# EnsembleSeven.net
KiCad netlist of a schematic drawn in EAGLE
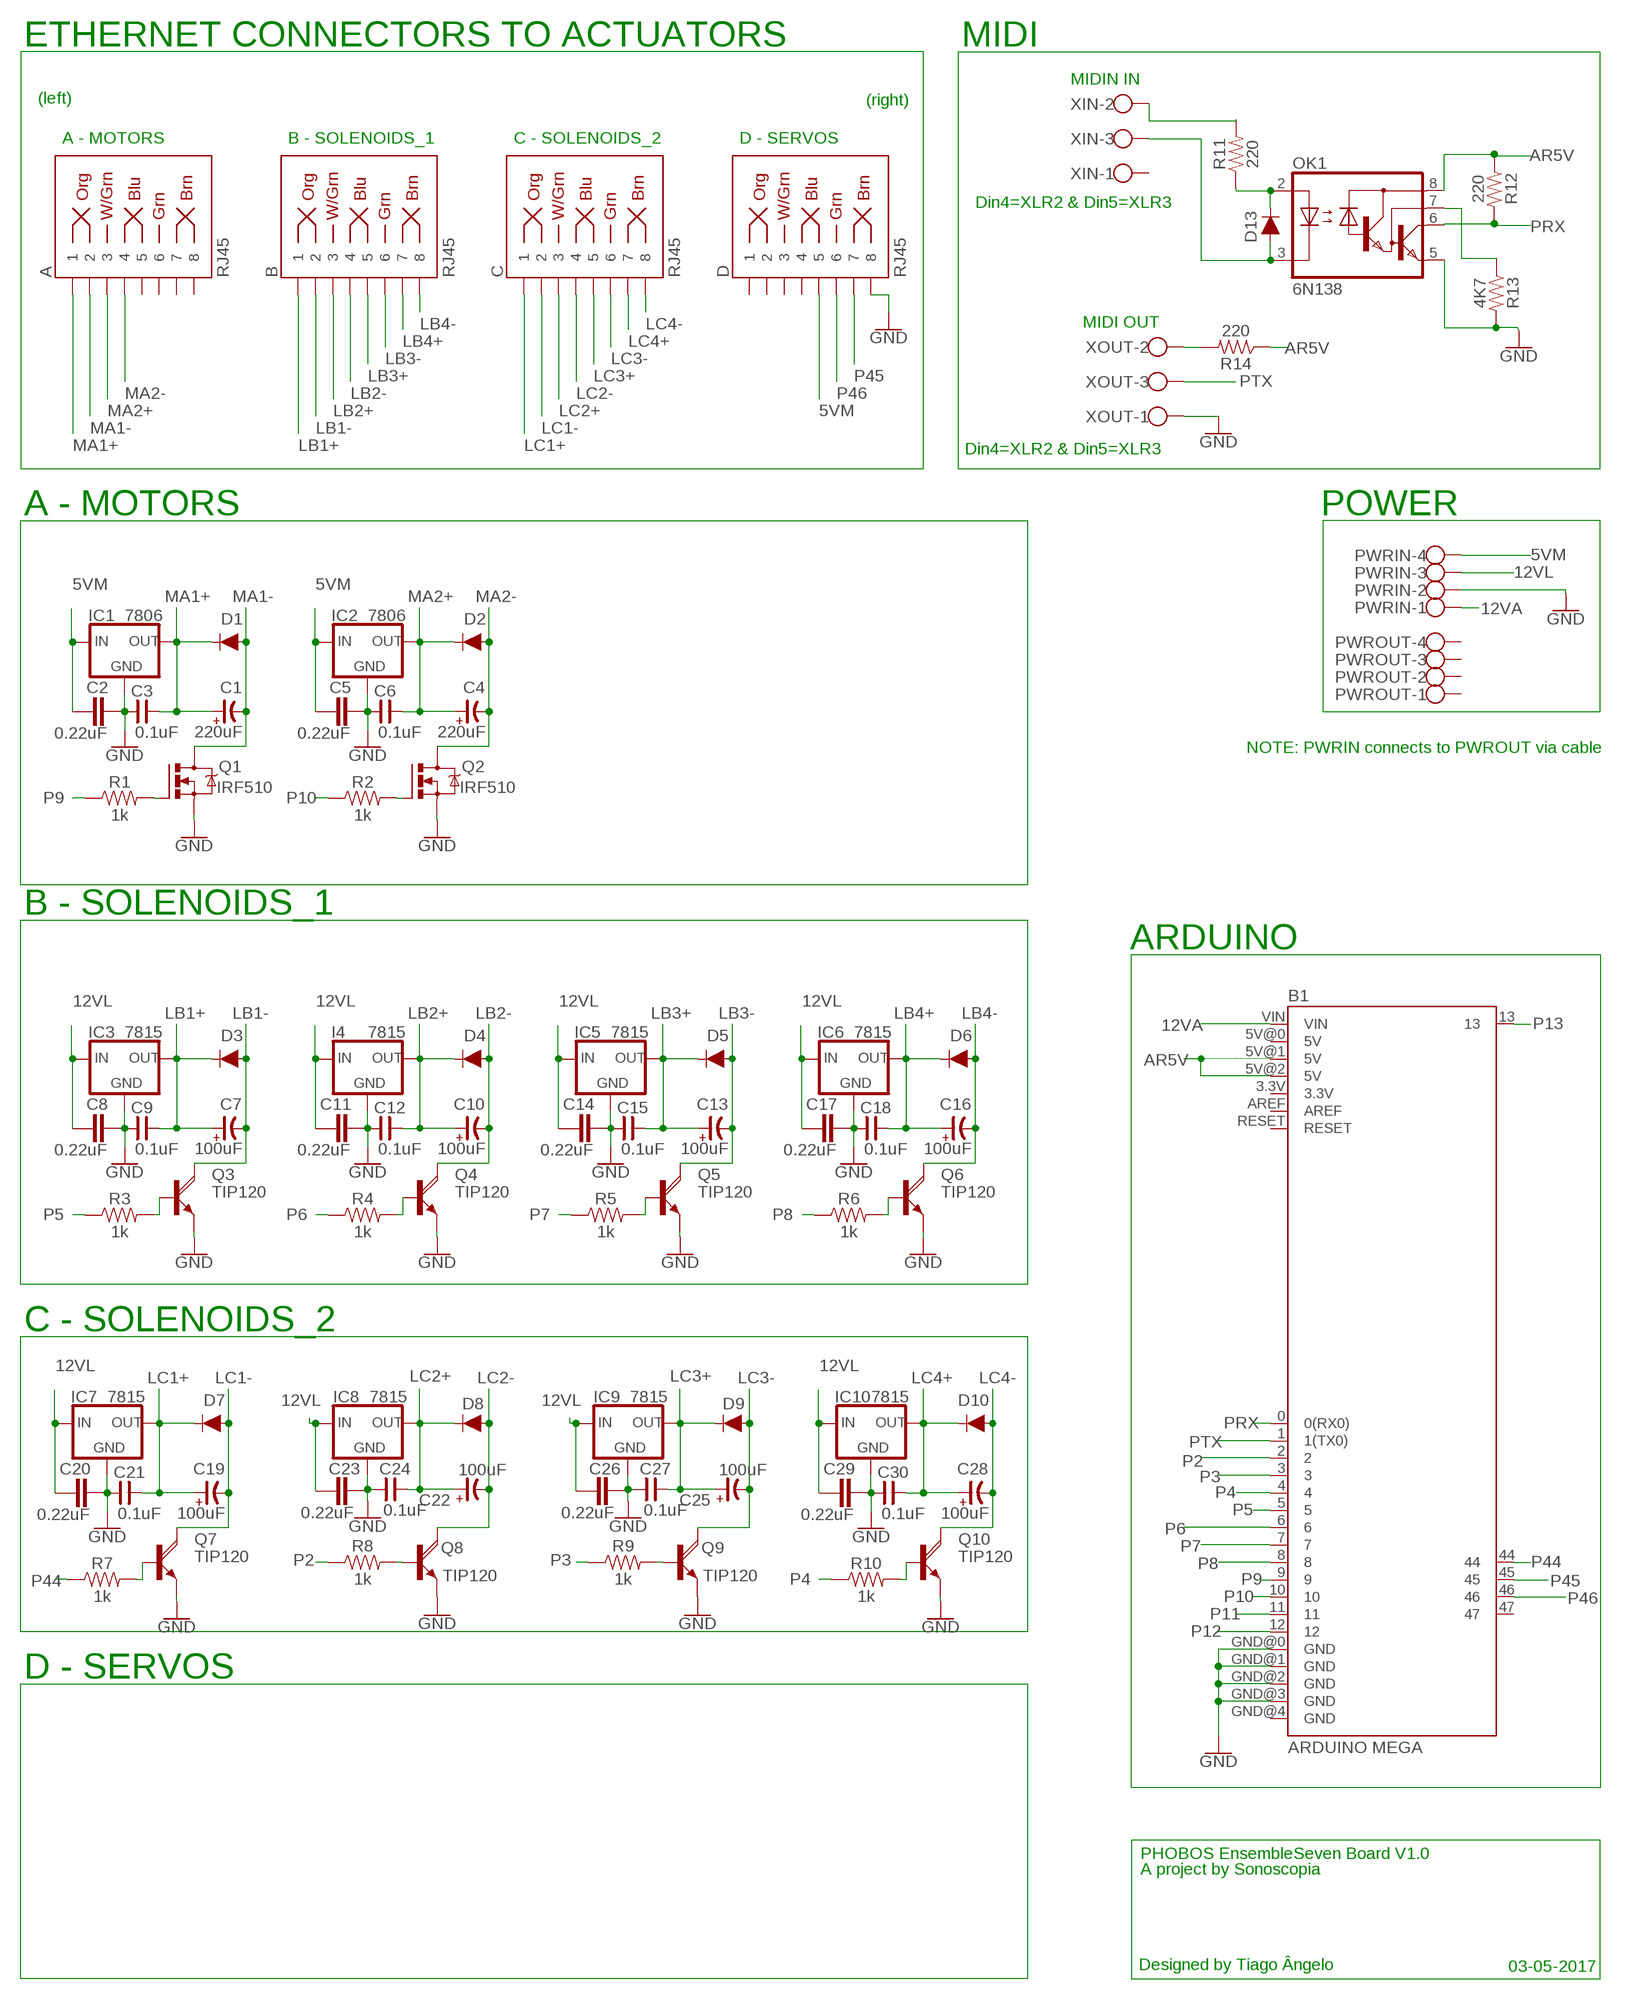
[diagram p0: schematic, sheet 1]

(export (version "E")
  (design (tool "Eeschema 10.0.6"))
  (components
    (comp (ref "A")
      (value "RJ45")
      (footprint "eagle-import:RJ45-8")
      (libsource (lib "eagle-import") (part "RJ45-8"))
    )
    (comp (ref "B")
      (value "RJ45")
      (footprint "eagle-import:RJ45-8")
      (libsource (lib "eagle-import") (part "RJ45-8"))
    )
    (comp (ref "B1")
      (value "ARDUINO MEGA")
      (footprint "eagle-import:ARDUINO_MEGA")
      (libsource (lib "eagle-import") (part "ARDUINO_MEGA_R3FULL"))
    )
    (comp (ref "C")
      (value "RJ45")
      (footprint "eagle-import:RJ45-8")
      (libsource (lib "eagle-import") (part "RJ45-8"))
    )
    (comp (ref "C1")
      (value "220uF")
      (footprint "eagle-import:E-035X080")
      (libsource (lib "eagle-import") (part "CP-E-035X080"))
    )
    (comp (ref "C2")
      (value "0.22uF")
      (footprint "eagle-import:C5B3")
      (libsource (lib "eagle-import") (part "C5/3"))
    )
    (comp (ref "C3")
      (value "0.1uF")
      (footprint "eagle-import:C025-050X025")
      (libsource (lib "eagle-import") (part "CNP-C025-050X025"))
    )
    (comp (ref "C4")
      (value "220uF")
      (footprint "eagle-import:E-035X080")
      (libsource (lib "eagle-import") (part "CP-E-035X080"))
    )
    (comp (ref "C5")
      (value "0.22uF")
      (footprint "eagle-import:C5B3")
      (libsource (lib "eagle-import") (part "C5/3"))
    )
    (comp (ref "C6")
      (value "0.1uF")
      (footprint "eagle-import:C025-050X025")
      (libsource (lib "eagle-import") (part "CNP-C025-050X025"))
    )
    (comp (ref "C7")
      (value "100uF")
      (footprint "eagle-import:CAP-MASTER_E-020X050")
      (libsource (lib "eagle-import") (part "CAP-MASTER_CP-E-020X050"))
    )
    (comp (ref "C8")
      (value "0.22uF")
      (footprint "eagle-import:C5B3")
      (libsource (lib "eagle-import") (part "C5/3"))
    )
    (comp (ref "C9")
      (value "0.1uF")
      (footprint "eagle-import:C025-050X025")
      (libsource (lib "eagle-import") (part "CNP-C025-050X025"))
    )
    (comp (ref "C10")
      (value "100uF")
      (footprint "eagle-import:CAP-MASTER_E-020X050")
      (libsource (lib "eagle-import") (part "CAP-MASTER_CP-E-020X050"))
    )
    (comp (ref "C11")
      (value "0.22uF")
      (footprint "eagle-import:C5B3")
      (libsource (lib "eagle-import") (part "C5/3"))
    )
    (comp (ref "C12")
      (value "0.1uF")
      (footprint "eagle-import:C025-050X025")
      (libsource (lib "eagle-import") (part "CNP-C025-050X025"))
    )
    (comp (ref "C13")
      (value "100uF")
      (footprint "eagle-import:CAP-MASTER_E-020X050")
      (libsource (lib "eagle-import") (part "CAP-MASTER_CP-E-020X050"))
    )
    (comp (ref "C14")
      (value "0.22uF")
      (footprint "eagle-import:C5B3")
      (libsource (lib "eagle-import") (part "C5/3"))
    )
    (comp (ref "C15")
      (value "0.1uF")
      (footprint "eagle-import:C025-050X025")
      (libsource (lib "eagle-import") (part "CNP-C025-050X025"))
    )
    (comp (ref "C16")
      (value "100uF")
      (footprint "eagle-import:CAP-MASTER_E-020X050")
      (libsource (lib "eagle-import") (part "CAP-MASTER_CP-E-020X050"))
    )
    (comp (ref "C17")
      (value "0.22uF")
      (footprint "eagle-import:C5B3")
      (libsource (lib "eagle-import") (part "C5/3"))
    )
    (comp (ref "C18")
      (value "0.1uF")
      (footprint "eagle-import:C025-050X025")
      (libsource (lib "eagle-import") (part "CNP-C025-050X025"))
    )
    (comp (ref "C19")
      (value "100uF")
      (footprint "eagle-import:CAP-MASTER_E-020X050")
      (libsource (lib "eagle-import") (part "CAP-MASTER_CP-E-020X050"))
    )
    (comp (ref "C20")
      (value "0.22uF")
      (footprint "eagle-import:C5B3")
      (libsource (lib "eagle-import") (part "C5/3"))
    )
    (comp (ref "C21")
      (value "0.1uF")
      (footprint "eagle-import:C025-050X025")
      (libsource (lib "eagle-import") (part "CNP-C025-050X025"))
    )
    (comp (ref "C22")
      (value "100uF")
      (footprint "eagle-import:E-020X050")
      (libsource (lib "eagle-import") (part "CP-E-020X050"))
    )
    (comp (ref "C23")
      (value "0.22uF")
      (footprint "eagle-import:C5B3")
      (libsource (lib "eagle-import") (part "C5/3"))
    )
    (comp (ref "C24")
      (value "0.1uF")
      (footprint "eagle-import:C025-050X025")
      (libsource (lib "eagle-import") (part "CNP-C025-050X025"))
    )
    (comp (ref "C25")
      (value "100uF")
      (footprint "eagle-import:E-020X050")
      (libsource (lib "eagle-import") (part "CP-E-020X050"))
    )
    (comp (ref "C26")
      (value "0.22uF")
      (footprint "eagle-import:C5B3")
      (libsource (lib "eagle-import") (part "C5/3"))
    )
    (comp (ref "C27")
      (value "0.1uF")
      (footprint "eagle-import:C025-050X025")
      (libsource (lib "eagle-import") (part "CNP-C025-050X025"))
    )
    (comp (ref "C28")
      (value "100uF")
      (footprint "eagle-import:CAP-MASTER_E-020X050")
      (libsource (lib "eagle-import") (part "CAP-MASTER_CP-E-020X050"))
    )
    (comp (ref "C29")
      (value "0.22uF")
      (footprint "eagle-import:C5B3")
      (libsource (lib "eagle-import") (part "C5/3"))
    )
    (comp (ref "C30")
      (value "0.1uF")
      (footprint "eagle-import:C025-050X025")
      (libsource (lib "eagle-import") (part "CNP-C025-050X025"))
    )
    (comp (ref "D")
      (value "RJ45")
      (footprint "eagle-import:RJ45-8")
      (libsource (lib "eagle-import") (part "RJ45-8"))
    )
    (comp (ref "D1")
      (value "1A/50V/1.1V")
      (footprint "eagle-import:DIODE-1N4001-KIT")
      (libsource (lib "eagle-import") (part "DIODE-KIT2"))
    )
    (comp (ref "D2")
      (value "1A/50V/1.1V")
      (footprint "eagle-import:DIODE-1N4001-KIT")
      (libsource (lib "eagle-import") (part "DIODE-KIT2"))
    )
    (comp (ref "D3")
      (value "1A/50V/1.1V")
      (footprint "eagle-import:DIODE-1N4001-KIT")
      (libsource (lib "eagle-import") (part "DIODE-KIT2"))
    )
    (comp (ref "D4")
      (value "1A/50V/1.1V")
      (footprint "eagle-import:DIODE-1N4001-KIT")
      (libsource (lib "eagle-import") (part "DIODE-KIT2"))
    )
    (comp (ref "D5")
      (value "1A/50V/1.1V")
      (footprint "eagle-import:DIODE-1N4001-KIT")
      (libsource (lib "eagle-import") (part "DIODE-KIT2"))
    )
    (comp (ref "D6")
      (value "1A/50V/1.1V")
      (footprint "eagle-import:DIODE-1N4001-KIT")
      (libsource (lib "eagle-import") (part "DIODE-KIT2"))
    )
    (comp (ref "D7")
      (value "1A/50V/1.1V")
      (footprint "eagle-import:DIODE-1N4001-KIT")
      (libsource (lib "eagle-import") (part "DIODE-KIT2"))
    )
    (comp (ref "D8")
      (value "1A/50V/1.1V")
      (footprint "eagle-import:DIODE-1N4001-KIT")
      (libsource (lib "eagle-import") (part "DIODE-KIT2"))
    )
    (comp (ref "D9")
      (value "1A/50V/1.1V")
      (footprint "eagle-import:DIODE-1N4001-KIT")
      (libsource (lib "eagle-import") (part "DIODE-KIT2"))
    )
    (comp (ref "D10")
      (value "1A/50V/1.1V")
      (footprint "eagle-import:DIODE-1N4001-KIT")
      (libsource (lib "eagle-import") (part "DIODE-KIT2"))
    )
    (comp (ref "D13")
      (value "200mA/100V/1V")
      (footprint "eagle-import:DIODE-1N4148")
      (libsource (lib "eagle-import") (part "DIODE-1N4148"))
    )
    (comp (ref "I4")
      (value "7815")
      (footprint "eagle-import:78XXS")
      (libsource (lib "eagle-import") (part "78XXS"))
    )
    (comp (ref "IC1")
      (value "7806")
      (footprint "eagle-import:78XXS")
      (libsource (lib "eagle-import") (part "78XXS"))
    )
    (comp (ref "IC2")
      (value "7806")
      (footprint "eagle-import:78XXS")
      (libsource (lib "eagle-import") (part "78XXS"))
    )
    (comp (ref "IC3")
      (value "7815")
      (footprint "eagle-import:78XXS")
      (libsource (lib "eagle-import") (part "78XXS"))
    )
    (comp (ref "IC5")
      (value "7815")
      (footprint "eagle-import:78XXS")
      (libsource (lib "eagle-import") (part "78XXS"))
    )
    (comp (ref "IC6")
      (value "7815")
      (footprint "eagle-import:78XXS")
      (libsource (lib "eagle-import") (part "78XXS"))
    )
    (comp (ref "IC7")
      (value "7815")
      (footprint "eagle-import:78XXS")
      (libsource (lib "eagle-import") (part "78XXS"))
    )
    (comp (ref "IC8")
      (value "7815")
      (footprint "eagle-import:78XXS")
      (libsource (lib "eagle-import") (part "78XXS"))
    )
    (comp (ref "IC9")
      (value "7815")
      (footprint "eagle-import:78XXS")
      (libsource (lib "eagle-import") (part "78XXS"))
    )
    (comp (ref "IC10")
      (value "7815")
      (footprint "eagle-import:78XXS")
      (libsource (lib "eagle-import") (part "78XXS"))
    )
    (comp (ref "OK1")
      (value "6N138")
      (footprint "eagle-import:DIL08")
      (fields (field (name "MF") "VISHAY/TELEFUNKEN"))
      (libsource (lib "eagle-import") (part "6N138"))
    )
    (comp (ref "PWRIN")
      (value "W237-4")
      (footprint "eagle-import:W237-4")
      (libsource (lib "eagle-import") (part "W237-4"))
    )
    (comp (ref "PWROUT")
      (value "W237-4")
      (footprint "eagle-import:W237-4")
      (libsource (lib "eagle-import") (part "W237-4"))
    )
    (comp (ref "Q1")
      (value "IRF510")
      (footprint "eagle-import:TO220BV")
      (libsource (lib "eagle-import") (part "IRF520"))
    )
    (comp (ref "Q2")
      (value "IRF510")
      (footprint "eagle-import:TO220BV")
      (libsource (lib "eagle-import") (part "IRF520"))
    )
    (comp (ref "Q3")
      (value "TIP120")
      (footprint "eagle-import:ROCKETFARM_TO220AV")
      (libsource (lib "eagle-import") (part "ROCKETFARM_TIP120V"))
    )
    (comp (ref "Q4")
      (value "TIP120")
      (footprint "eagle-import:ROCKETFARM_TO220AV")
      (libsource (lib "eagle-import") (part "ROCKETFARM_TIP120V"))
    )
    (comp (ref "Q5")
      (value "TIP120")
      (footprint "eagle-import:ROCKETFARM_TO220AV")
      (libsource (lib "eagle-import") (part "ROCKETFARM_TIP120V"))
    )
    (comp (ref "Q6")
      (value "TIP120")
      (footprint "eagle-import:ROCKETFARM_TO220AV")
      (libsource (lib "eagle-import") (part "ROCKETFARM_TIP120V"))
    )
    (comp (ref "Q7")
      (value "TIP120")
      (footprint "eagle-import:ROCKETFARM_TO220AV")
      (libsource (lib "eagle-import") (part "ROCKETFARM_TIP120V"))
    )
    (comp (ref "Q8")
      (value "TIP120")
      (footprint "eagle-import:TO220AV")
      (libsource (lib "eagle-import") (part "TIP120V"))
    )
    (comp (ref "Q9")
      (value "TIP120")
      (footprint "eagle-import:TO220AV")
      (libsource (lib "eagle-import") (part "TIP120V"))
    )
    (comp (ref "Q10")
      (value "TIP120")
      (footprint "eagle-import:ROCKETFARM_TO220AV")
      (libsource (lib "eagle-import") (part "ROCKETFARM_TIP120V"))
    )
    (comp (ref "R1")
      (value "1k")
      (footprint "eagle-import:AXIAL-0.1")
      (libsource (lib "eagle-import") (part "1KOHM-VERT-1/4W-1%"))
    )
    (comp (ref "R2")
      (value "1k")
      (footprint "eagle-import:AXIAL-0.1")
      (libsource (lib "eagle-import") (part "1KOHM-VERT-1/4W-1%"))
    )
    (comp (ref "R3")
      (value "1k")
      (footprint "eagle-import:AXIAL-0.1")
      (libsource (lib "eagle-import") (part "1KOHM-VERT-1/4W-1%"))
    )
    (comp (ref "R4")
      (value "1k")
      (footprint "eagle-import:AXIAL-0.1")
      (libsource (lib "eagle-import") (part "1KOHM-VERT-1/4W-1%"))
    )
    (comp (ref "R5")
      (value "1k")
      (footprint "eagle-import:AXIAL-0.1")
      (libsource (lib "eagle-import") (part "1KOHM-VERT-1/4W-1%"))
    )
    (comp (ref "R6")
      (value "1k")
      (footprint "eagle-import:AXIAL-0.1")
      (libsource (lib "eagle-import") (part "1KOHM-VERT-1/4W-1%"))
    )
    (comp (ref "R7")
      (value "1k")
      (footprint "eagle-import:AXIAL-0.1")
      (libsource (lib "eagle-import") (part "1KOHM-VERT-1/4W-1%"))
    )
    (comp (ref "R8")
      (value "1k")
      (footprint "eagle-import:AXIAL-0.1")
      (libsource (lib "eagle-import") (part "1KOHM-VERT-1/4W-1%"))
    )
    (comp (ref "R9")
      (value "1k")
      (footprint "eagle-import:AXIAL-0.1")
      (libsource (lib "eagle-import") (part "1KOHM-VERT-1/4W-1%"))
    )
    (comp (ref "R10")
      (value "1k")
      (footprint "eagle-import:AXIAL-0.1")
      (libsource (lib "eagle-import") (part "1KOHM-VERT-1/4W-1%"))
    )
    (comp (ref "R11")
      (value "220")
      (footprint "eagle-import:AXIAL-0.3")
      (libsource (lib "eagle-import") (part "1KOHM-HORIZ-1/4W-5%"))
    )
    (comp (ref "R12")
      (value "220")
      (footprint "eagle-import:AXIAL-0.3")
      (libsource (lib "eagle-import") (part "1KOHM-HORIZ-1/4W-5%"))
    )
    (comp (ref "R13")
      (value "4K7")
      (footprint "eagle-import:AXIAL-0.3")
      (libsource (lib "eagle-import") (part "1KOHM-HORIZ-1/4W-5%"))
    )
    (comp (ref "R14")
      (value "220")
      (footprint "eagle-import:AXIAL-0.3")
      (libsource (lib "eagle-import") (part "1KOHM-HORIZ-1/4W-5%"))
    )
    (comp (ref "XIN")
      (value "W237-103")
      (footprint "eagle-import:W237-103")
      (fields (field (name "MPN") "237-103"))
      (libsource (lib "eagle-import") (part "W237-103"))
    )
    (comp (ref "XOUT")
      (value "W237-103")
      (footprint "eagle-import:W237-103")
      (fields (field (name "MPN") "237-103"))
      (libsource (lib "eagle-import") (part "W237-103"))
    )
  )
  (nets
    (net (code "1") (name "/5VM") (class "Default")
      (node (ref "C2") (pin "1") (pinfunction "1_1") (pintype "passive"))
      (node (ref "C5") (pin "1") (pinfunction "1_1") (pintype "passive"))
      (node (ref "D") (pin "5") (pinfunction "5_5") (pintype "bidirectional"))
      (node (ref "IC1") (pin "IN") (pinfunction "IN_IN") (pintype "input"))
      (node (ref "IC2") (pin "IN") (pinfunction "IN_IN") (pintype "input"))
      (node (ref "PWRIN") (pin "4") (pinfunction "KL_4") (pintype "passive"))
    )
    (net (code "2") (name "/12VA") (class "Default")
      (node (ref "B1") (pin "VIN") (pinfunction "VIN_VIN") (pintype "bidirectional"))
      (node (ref "PWRIN") (pin "1") (pinfunction "KL_1") (pintype "passive"))
    )
    (net (code "3") (name "/12VL") (class "Default")
      (node (ref "C11") (pin "1") (pinfunction "1_1") (pintype "passive"))
      (node (ref "C14") (pin "1") (pinfunction "1_1") (pintype "passive"))
      (node (ref "C17") (pin "1") (pinfunction "1_1") (pintype "passive"))
      (node (ref "C20") (pin "1") (pinfunction "1_1") (pintype "passive"))
      (node (ref "C23") (pin "1") (pinfunction "1_1") (pintype "passive"))
      (node (ref "C26") (pin "1") (pinfunction "1_1") (pintype "passive"))
      (node (ref "C29") (pin "1") (pinfunction "1_1") (pintype "passive"))
      (node (ref "C8") (pin "1") (pinfunction "1_1") (pintype "passive"))
      (node (ref "I4") (pin "IN") (pinfunction "IN_IN") (pintype "input"))
      (node (ref "IC10") (pin "IN") (pinfunction "IN_IN") (pintype "input"))
      (node (ref "IC3") (pin "IN") (pinfunction "IN_IN") (pintype "input"))
      (node (ref "IC5") (pin "IN") (pinfunction "IN_IN") (pintype "input"))
      (node (ref "IC6") (pin "IN") (pinfunction "IN_IN") (pintype "input"))
      (node (ref "IC7") (pin "IN") (pinfunction "IN_IN") (pintype "input"))
      (node (ref "IC8") (pin "IN") (pinfunction "IN_IN") (pintype "input"))
      (node (ref "IC9") (pin "IN") (pinfunction "IN_IN") (pintype "input"))
      (node (ref "PWRIN") (pin "3") (pinfunction "KL_3") (pintype "passive"))
    )
    (net (code "4") (name "/AR5V") (class "Default")
      (node (ref "B1") (pin "5V@1") (pinfunction "5V_5V@1") (pintype "bidirectional"))
      (node (ref "B1") (pin "5V@2") (pinfunction "5V_5V@2") (pintype "bidirectional"))
      (node (ref "OK1") (pin "8") (pinfunction "VCC_8") (pintype "passive"))
      (node (ref "R12") (pin "P$1") (pinfunction "1_P$1") (pintype "passive"))
      (node (ref "R14") (pin "P$1") (pinfunction "1_P$1") (pintype "passive"))
    )
    (net (code "5") (name "/LB1+") (class "Default")
      (node (ref "B") (pin "1") (pinfunction "1_1") (pintype "bidirectional"))
      (node (ref "C7") (pin "+") (pinfunction "+_+") (pintype "passive"))
      (node (ref "C9") (pin "2") (pinfunction "2_2") (pintype "passive"))
      (node (ref "D3") (pin "C") (pinfunction "C_C") (pintype "passive"))
      (node (ref "IC3") (pin "OUT") (pinfunction "OUT_OUT") (pintype "passive"))
    )
    (net (code "6") (name "/LB1-") (class "Default")
      (node (ref "B") (pin "2") (pinfunction "2_2") (pintype "bidirectional"))
      (node (ref "C7") (pin "-") (pinfunction "-_-") (pintype "passive"))
      (node (ref "D3") (pin "A") (pinfunction "A_A") (pintype "passive"))
      (node (ref "Q3") (pin "C") (pinfunction "C_C") (pintype "passive"))
    )
    (net (code "7") (name "/LB2+") (class "Default")
      (node (ref "B") (pin "3") (pinfunction "3_3") (pintype "bidirectional"))
      (node (ref "C10") (pin "+") (pinfunction "+_+") (pintype "passive"))
      (node (ref "C12") (pin "2") (pinfunction "2_2") (pintype "passive"))
      (node (ref "D4") (pin "C") (pinfunction "C_C") (pintype "passive"))
      (node (ref "I4") (pin "OUT") (pinfunction "OUT_OUT") (pintype "passive"))
    )
    (net (code "8") (name "/LB2-") (class "Default")
      (node (ref "B") (pin "4") (pinfunction "4_4") (pintype "bidirectional"))
      (node (ref "C10") (pin "-") (pinfunction "-_-") (pintype "passive"))
      (node (ref "D4") (pin "A") (pinfunction "A_A") (pintype "passive"))
      (node (ref "Q4") (pin "C") (pinfunction "C_C") (pintype "passive"))
    )
    (net (code "9") (name "/LB3+") (class "Default")
      (node (ref "B") (pin "5") (pinfunction "5_5") (pintype "bidirectional"))
      (node (ref "C13") (pin "+") (pinfunction "+_+") (pintype "passive"))
      (node (ref "C15") (pin "2") (pinfunction "2_2") (pintype "passive"))
      (node (ref "D5") (pin "C") (pinfunction "C_C") (pintype "passive"))
      (node (ref "IC5") (pin "OUT") (pinfunction "OUT_OUT") (pintype "passive"))
    )
    (net (code "10") (name "/LB3-") (class "Default")
      (node (ref "B") (pin "6") (pinfunction "6_6") (pintype "bidirectional"))
      (node (ref "C13") (pin "-") (pinfunction "-_-") (pintype "passive"))
      (node (ref "D5") (pin "A") (pinfunction "A_A") (pintype "passive"))
      (node (ref "Q5") (pin "C") (pinfunction "C_C") (pintype "passive"))
    )
    (net (code "11") (name "/LB4+") (class "Default")
      (node (ref "B") (pin "7") (pinfunction "7_7") (pintype "bidirectional"))
      (node (ref "C16") (pin "+") (pinfunction "+_+") (pintype "passive"))
      (node (ref "C18") (pin "2") (pinfunction "2_2") (pintype "passive"))
      (node (ref "D6") (pin "C") (pinfunction "C_C") (pintype "passive"))
      (node (ref "IC6") (pin "OUT") (pinfunction "OUT_OUT") (pintype "passive"))
    )
    (net (code "12") (name "/LB4-") (class "Default")
      (node (ref "B") (pin "8") (pinfunction "8_8") (pintype "bidirectional"))
      (node (ref "C16") (pin "-") (pinfunction "-_-") (pintype "passive"))
      (node (ref "D6") (pin "A") (pinfunction "A_A") (pintype "passive"))
      (node (ref "Q6") (pin "C") (pinfunction "C_C") (pintype "passive"))
    )
    (net (code "13") (name "/LC1+") (class "Default")
      (node (ref "C") (pin "1") (pinfunction "1_1") (pintype "bidirectional"))
      (node (ref "C19") (pin "+") (pinfunction "+_+") (pintype "passive"))
      (node (ref "C21") (pin "2") (pinfunction "2_2") (pintype "passive"))
      (node (ref "D7") (pin "C") (pinfunction "C_C") (pintype "passive"))
      (node (ref "IC7") (pin "OUT") (pinfunction "OUT_OUT") (pintype "passive"))
    )
    (net (code "14") (name "/LC1-") (class "Default")
      (node (ref "C") (pin "2") (pinfunction "2_2") (pintype "bidirectional"))
      (node (ref "C19") (pin "-") (pinfunction "-_-") (pintype "passive"))
      (node (ref "D7") (pin "A") (pinfunction "A_A") (pintype "passive"))
      (node (ref "Q7") (pin "C") (pinfunction "C_C") (pintype "passive"))
    )
    (net (code "15") (name "/LC2+") (class "Default")
      (node (ref "C") (pin "3") (pinfunction "3_3") (pintype "bidirectional"))
      (node (ref "C22") (pin "+") (pinfunction "+_+") (pintype "passive"))
      (node (ref "C24") (pin "2") (pinfunction "2_2") (pintype "passive"))
      (node (ref "D8") (pin "C") (pinfunction "C_C") (pintype "passive"))
      (node (ref "IC8") (pin "OUT") (pinfunction "OUT_OUT") (pintype "passive"))
    )
    (net (code "16") (name "/LC2-") (class "Default")
      (node (ref "C") (pin "4") (pinfunction "4_4") (pintype "bidirectional"))
      (node (ref "C22") (pin "-") (pinfunction "-_-") (pintype "passive"))
      (node (ref "D8") (pin "A") (pinfunction "A_A") (pintype "passive"))
      (node (ref "Q8") (pin "C") (pinfunction "C_C") (pintype "passive"))
    )
    (net (code "17") (name "/LC3+") (class "Default")
      (node (ref "C") (pin "5") (pinfunction "5_5") (pintype "bidirectional"))
      (node (ref "C25") (pin "+") (pinfunction "+_+") (pintype "passive"))
      (node (ref "C27") (pin "2") (pinfunction "2_2") (pintype "passive"))
      (node (ref "D9") (pin "C") (pinfunction "C_C") (pintype "passive"))
      (node (ref "IC9") (pin "OUT") (pinfunction "OUT_OUT") (pintype "passive"))
    )
    (net (code "18") (name "/LC3-") (class "Default")
      (node (ref "C") (pin "6") (pinfunction "6_6") (pintype "bidirectional"))
      (node (ref "C25") (pin "-") (pinfunction "-_-") (pintype "passive"))
      (node (ref "D9") (pin "A") (pinfunction "A_A") (pintype "passive"))
      (node (ref "Q9") (pin "C") (pinfunction "C_C") (pintype "passive"))
    )
    (net (code "19") (name "/LC4+") (class "Default")
      (node (ref "C") (pin "7") (pinfunction "7_7") (pintype "bidirectional"))
      (node (ref "C28") (pin "+") (pinfunction "+_+") (pintype "passive"))
      (node (ref "C30") (pin "2") (pinfunction "2_2") (pintype "passive"))
      (node (ref "D10") (pin "C") (pinfunction "C_C") (pintype "passive"))
      (node (ref "IC10") (pin "OUT") (pinfunction "OUT_OUT") (pintype "passive"))
    )
    (net (code "20") (name "/LC4-") (class "Default")
      (node (ref "C") (pin "8") (pinfunction "8_8") (pintype "bidirectional"))
      (node (ref "C28") (pin "-") (pinfunction "-_-") (pintype "passive"))
      (node (ref "D10") (pin "A") (pinfunction "A_A") (pintype "passive"))
      (node (ref "Q10") (pin "C") (pinfunction "C_C") (pintype "passive"))
    )
    (net (code "21") (name "/MA1+") (class "Default")
      (node (ref "A") (pin "1") (pinfunction "1_1") (pintype "bidirectional"))
      (node (ref "C1") (pin "+") (pinfunction "+_+") (pintype "passive"))
      (node (ref "C3") (pin "2") (pinfunction "2_2") (pintype "passive"))
      (node (ref "D1") (pin "C") (pinfunction "C_C") (pintype "passive"))
      (node (ref "IC1") (pin "OUT") (pinfunction "OUT_OUT") (pintype "passive"))
    )
    (net (code "22") (name "/MA1-") (class "Default")
      (node (ref "A") (pin "2") (pinfunction "2_2") (pintype "bidirectional"))
      (node (ref "C1") (pin "-") (pinfunction "-_-") (pintype "passive"))
      (node (ref "D1") (pin "A") (pinfunction "A_A") (pintype "passive"))
      (node (ref "Q1") (pin "D") (pinfunction "D_D") (pintype "passive"))
    )
    (net (code "23") (name "/MA2+") (class "Default")
      (node (ref "A") (pin "3") (pinfunction "3_3") (pintype "bidirectional"))
      (node (ref "C4") (pin "+") (pinfunction "+_+") (pintype "passive"))
      (node (ref "C6") (pin "2") (pinfunction "2_2") (pintype "passive"))
      (node (ref "D2") (pin "C") (pinfunction "C_C") (pintype "passive"))
      (node (ref "IC2") (pin "OUT") (pinfunction "OUT_OUT") (pintype "passive"))
    )
    (net (code "24") (name "/MA2-") (class "Default")
      (node (ref "A") (pin "4") (pinfunction "4_4") (pintype "bidirectional"))
      (node (ref "C4") (pin "-") (pinfunction "-_-") (pintype "passive"))
      (node (ref "D2") (pin "A") (pinfunction "A_A") (pintype "passive"))
      (node (ref "Q2") (pin "D") (pinfunction "D_D") (pintype "passive"))
    )
    (net (code "25") (name "/P2") (class "Default")
      (node (ref "B1") (pin "2") (pinfunction "2_2") (pintype "bidirectional"))
      (node (ref "R8") (pin "P$1") (pinfunction "1_P$1") (pintype "passive"))
    )
    (net (code "26") (name "/P3") (class "Default")
      (node (ref "B1") (pin "3") (pinfunction "3_3") (pintype "bidirectional"))
      (node (ref "R9") (pin "P$1") (pinfunction "1_P$1") (pintype "passive"))
    )
    (net (code "27") (name "/P4") (class "Default")
      (node (ref "B1") (pin "4") (pinfunction "4_4") (pintype "bidirectional"))
      (node (ref "R10") (pin "P$1") (pinfunction "1_P$1") (pintype "passive"))
    )
    (net (code "28") (name "/P5") (class "Default")
      (node (ref "B1") (pin "5") (pinfunction "5_5") (pintype "bidirectional"))
      (node (ref "R3") (pin "P$1") (pinfunction "1_P$1") (pintype "passive"))
    )
    (net (code "29") (name "/P6") (class "Default")
      (node (ref "B1") (pin "6") (pinfunction "6_6") (pintype "bidirectional"))
      (node (ref "R4") (pin "P$1") (pinfunction "1_P$1") (pintype "passive"))
    )
    (net (code "30") (name "/P7") (class "Default")
      (node (ref "B1") (pin "7") (pinfunction "7_7") (pintype "bidirectional"))
      (node (ref "R5") (pin "P$1") (pinfunction "1_P$1") (pintype "passive"))
    )
    (net (code "31") (name "/P8") (class "Default")
      (node (ref "B1") (pin "8") (pinfunction "8_8") (pintype "bidirectional"))
      (node (ref "R6") (pin "P$1") (pinfunction "1_P$1") (pintype "passive"))
    )
    (net (code "32") (name "/P9") (class "Default")
      (node (ref "B1") (pin "9") (pinfunction "9_9") (pintype "bidirectional"))
      (node (ref "R1") (pin "P$1") (pinfunction "1_P$1") (pintype "passive"))
    )
    (net (code "33") (name "/P10") (class "Default")
      (node (ref "B1") (pin "10") (pinfunction "10_10") (pintype "bidirectional"))
      (node (ref "R2") (pin "P$1") (pinfunction "1_P$1") (pintype "passive"))
    )
    (net (code "34") (name "/P11") (class "Default")
      (node (ref "B1") (pin "11") (pinfunction "11_11") (pintype "bidirectional"))
    )
    (net (code "35") (name "/P12") (class "Default")
      (node (ref "B1") (pin "12") (pinfunction "12_12") (pintype "bidirectional"))
    )
    (net (code "36") (name "/P13") (class "Default")
      (node (ref "B1") (pin "13") (pinfunction "13_13") (pintype "bidirectional"))
    )
    (net (code "37") (name "/P44") (class "Default")
      (node (ref "B1") (pin "44") (pinfunction "44_44") (pintype "bidirectional"))
      (node (ref "R7") (pin "P$1") (pinfunction "1_P$1") (pintype "passive"))
    )
    (net (code "38") (name "/P45") (class "Default")
      (node (ref "B1") (pin "45") (pinfunction "45_45") (pintype "bidirectional"))
      (node (ref "D") (pin "7") (pinfunction "7_7") (pintype "bidirectional"))
    )
    (net (code "39") (name "/P46") (class "Default")
      (node (ref "B1") (pin "46") (pinfunction "46_46") (pintype "bidirectional"))
      (node (ref "D") (pin "6") (pinfunction "6_6") (pintype "bidirectional"))
    )
    (net (code "40") (name "/PRX") (class "Default")
      (node (ref "B1") (pin "0") (pinfunction "0(RX0)_0") (pintype "bidirectional"))
      (node (ref "OK1") (pin "6") (pinfunction "VO_6") (pintype "passive"))
      (node (ref "R12") (pin "P$2") (pinfunction "2_P$2") (pintype "passive"))
    )
    (net (code "41") (name "/PTX") (class "Default")
      (node (ref "B1") (pin "1") (pinfunction "1(TX0)_1") (pintype "bidirectional"))
      (node (ref "XOUT") (pin "3") (pinfunction "KL_3") (pintype "passive"))
    )
    (net (code "42") (name "GND") (class "Default")
      (node (ref "B1") (pin "GND@0") (pinfunction "GND_GND@0") (pintype "bidirectional"))
      (node (ref "B1") (pin "GND@1") (pinfunction "GND_GND@1") (pintype "bidirectional"))
      (node (ref "B1") (pin "GND@2") (pinfunction "GND_GND@2") (pintype "bidirectional"))
      (node (ref "B1") (pin "GND@3") (pinfunction "GND_GND@3") (pintype "bidirectional"))
      (node (ref "C11") (pin "2") (pinfunction "2_2") (pintype "passive"))
      (node (ref "C12") (pin "1") (pinfunction "1_1") (pintype "passive"))
      (node (ref "C14") (pin "2") (pinfunction "2_2") (pintype "passive"))
      (node (ref "C15") (pin "1") (pinfunction "1_1") (pintype "passive"))
      (node (ref "C17") (pin "2") (pinfunction "2_2") (pintype "passive"))
      (node (ref "C18") (pin "1") (pinfunction "1_1") (pintype "passive"))
      (node (ref "C2") (pin "2") (pinfunction "2_2") (pintype "passive"))
      (node (ref "C20") (pin "2") (pinfunction "2_2") (pintype "passive"))
      (node (ref "C21") (pin "1") (pinfunction "1_1") (pintype "passive"))
      (node (ref "C23") (pin "2") (pinfunction "2_2") (pintype "passive"))
      (node (ref "C24") (pin "1") (pinfunction "1_1") (pintype "passive"))
      (node (ref "C26") (pin "2") (pinfunction "2_2") (pintype "passive"))
      (node (ref "C27") (pin "1") (pinfunction "1_1") (pintype "passive"))
      (node (ref "C29") (pin "2") (pinfunction "2_2") (pintype "passive"))
      (node (ref "C3") (pin "1") (pinfunction "1_1") (pintype "passive"))
      (node (ref "C30") (pin "1") (pinfunction "1_1") (pintype "passive"))
      (node (ref "C5") (pin "2") (pinfunction "2_2") (pintype "passive"))
      (node (ref "C6") (pin "1") (pinfunction "1_1") (pintype "passive"))
      (node (ref "C8") (pin "2") (pinfunction "2_2") (pintype "passive"))
      (node (ref "C9") (pin "1") (pinfunction "1_1") (pintype "passive"))
      (node (ref "D") (pin "8") (pinfunction "8_8") (pintype "bidirectional"))
      (node (ref "I4") (pin "GND") (pinfunction "GND_GND") (pintype "input"))
      (node (ref "IC1") (pin "GND") (pinfunction "GND_GND") (pintype "input"))
      (node (ref "IC10") (pin "GND") (pinfunction "GND_GND") (pintype "input"))
      (node (ref "IC2") (pin "GND") (pinfunction "GND_GND") (pintype "input"))
      (node (ref "IC3") (pin "GND") (pinfunction "GND_GND") (pintype "input"))
      (node (ref "IC5") (pin "GND") (pinfunction "GND_GND") (pintype "input"))
      (node (ref "IC6") (pin "GND") (pinfunction "GND_GND") (pintype "input"))
      (node (ref "IC7") (pin "GND") (pinfunction "GND_GND") (pintype "input"))
      (node (ref "IC8") (pin "GND") (pinfunction "GND_GND") (pintype "input"))
      (node (ref "IC9") (pin "GND") (pinfunction "GND_GND") (pintype "input"))
      (node (ref "OK1") (pin "5") (pinfunction "GND_5") (pintype "passive"))
      (node (ref "PWRIN") (pin "2") (pinfunction "KL_2") (pintype "passive"))
      (node (ref "Q1") (pin "S") (pinfunction "S_S") (pintype "passive"))
      (node (ref "Q10") (pin "E") (pinfunction "E_E") (pintype "passive"))
      (node (ref "Q2") (pin "S") (pinfunction "S_S") (pintype "passive"))
      (node (ref "Q3") (pin "E") (pinfunction "E_E") (pintype "passive"))
      (node (ref "Q4") (pin "E") (pinfunction "E_E") (pintype "passive"))
      (node (ref "Q5") (pin "E") (pinfunction "E_E") (pintype "passive"))
      (node (ref "Q6") (pin "E") (pinfunction "E_E") (pintype "passive"))
      (node (ref "Q7") (pin "E") (pinfunction "E_E") (pintype "passive"))
      (node (ref "Q8") (pin "E") (pinfunction "E_E") (pintype "passive"))
      (node (ref "Q9") (pin "E") (pinfunction "E_E") (pintype "passive"))
      (node (ref "R13") (pin "P$2") (pinfunction "2_P$2") (pintype "passive"))
      (node (ref "XOUT") (pin "1") (pinfunction "KL_1") (pintype "passive"))
    )
    (net (code "43") (name "Net-(OK1-A)") (class "Default")
      (node (ref "D13") (pin "C") (pinfunction "C_C") (pintype "passive"))
      (node (ref "OK1") (pin "2") (pinfunction "A_2") (pintype "passive"))
      (node (ref "R11") (pin "P$1") (pinfunction "1_P$1") (pintype "passive"))
    )
    (net (code "44") (name "Net-(OK1-C)") (class "Default")
      (node (ref "D13") (pin "A") (pinfunction "A_A") (pintype "passive"))
      (node (ref "OK1") (pin "3") (pinfunction "C_3") (pintype "passive"))
      (node (ref "XIN") (pin "3") (pinfunction "KL_3") (pintype "passive"))
    )
    (net (code "45") (name "Net-(OK1-VB)") (class "Default")
      (node (ref "OK1") (pin "7") (pinfunction "VB_7") (pintype "passive"))
      (node (ref "R13") (pin "P$1") (pinfunction "1_P$1") (pintype "passive"))
    )
    (net (code "46") (name "Net-(R1-2)") (class "Default")
      (node (ref "Q1") (pin "G") (pinfunction "G_G") (pintype "passive"))
      (node (ref "R1") (pin "P$2") (pinfunction "2_P$2") (pintype "passive"))
    )
    (net (code "47") (name "Net-(R2-2)") (class "Default")
      (node (ref "Q2") (pin "G") (pinfunction "G_G") (pintype "passive"))
      (node (ref "R2") (pin "P$2") (pinfunction "2_P$2") (pintype "passive"))
    )
    (net (code "48") (name "Net-(R3-2)") (class "Default")
      (node (ref "Q3") (pin "B") (pinfunction "B_B") (pintype "passive"))
      (node (ref "R3") (pin "P$2") (pinfunction "2_P$2") (pintype "passive"))
    )
    (net (code "49") (name "Net-(R4-2)") (class "Default")
      (node (ref "Q4") (pin "B") (pinfunction "B_B") (pintype "passive"))
      (node (ref "R4") (pin "P$2") (pinfunction "2_P$2") (pintype "passive"))
    )
    (net (code "50") (name "Net-(R5-2)") (class "Default")
      (node (ref "Q5") (pin "B") (pinfunction "B_B") (pintype "passive"))
      (node (ref "R5") (pin "P$2") (pinfunction "2_P$2") (pintype "passive"))
    )
    (net (code "51") (name "Net-(R6-2)") (class "Default")
      (node (ref "Q6") (pin "B") (pinfunction "B_B") (pintype "passive"))
      (node (ref "R6") (pin "P$2") (pinfunction "2_P$2") (pintype "passive"))
    )
    (net (code "52") (name "Net-(R7-2)") (class "Default")
      (node (ref "Q7") (pin "B") (pinfunction "B_B") (pintype "passive"))
      (node (ref "R7") (pin "P$2") (pinfunction "2_P$2") (pintype "passive"))
    )
    (net (code "53") (name "Net-(R8-2)") (class "Default")
      (node (ref "Q8") (pin "B") (pinfunction "B_B") (pintype "passive"))
      (node (ref "R8") (pin "P$2") (pinfunction "2_P$2") (pintype "passive"))
    )
    (net (code "54") (name "Net-(R9-2)") (class "Default")
      (node (ref "Q9") (pin "B") (pinfunction "B_B") (pintype "passive"))
      (node (ref "R9") (pin "P$2") (pinfunction "2_P$2") (pintype "passive"))
    )
    (net (code "55") (name "Net-(R10-2)") (class "Default")
      (node (ref "Q10") (pin "B") (pinfunction "B_B") (pintype "passive"))
      (node (ref "R10") (pin "P$2") (pinfunction "2_P$2") (pintype "passive"))
    )
    (net (code "56") (name "Net-(R11-2)") (class "Default")
      (node (ref "R11") (pin "P$2") (pinfunction "2_P$2") (pintype "passive"))
      (node (ref "XIN") (pin "2") (pinfunction "KL_2") (pintype "passive"))
    )
    (net (code "57") (name "Net-(R14-2)") (class "Default")
      (node (ref "R14") (pin "P$2") (pinfunction "2_P$2") (pintype "passive"))
      (node (ref "XOUT") (pin "2") (pinfunction "KL_2") (pintype "passive"))
    )
    (net (code "58") (name "unconnected-(A-Pad5)") (class "Default")
      (node (ref "A") (pin "5") (pinfunction "5_5") (pintype "bidirectional"))
    )
    (net (code "59") (name "unconnected-(A-Pad6)") (class "Default")
      (node (ref "A") (pin "6") (pinfunction "6_6") (pintype "bidirectional"))
    )
    (net (code "60") (name "unconnected-(A-Pad7)") (class "Default")
      (node (ref "A") (pin "7") (pinfunction "7_7") (pintype "bidirectional"))
    )
    (net (code "61") (name "unconnected-(A-Pad8)") (class "Default")
      (node (ref "A") (pin "8") (pinfunction "8_8") (pintype "bidirectional"))
    )
    (net (code "62") (name "unconnected-(B1-5V-Pad5V@0)") (class "Default")
      (node (ref "B1") (pin "5V@0") (pinfunction "5V_5V@0") (pintype "bidirectional"))
    )
    (net (code "63") (name "unconnected-(B1-GND-PadGND@4)") (class "Default")
      (node (ref "B1") (pin "GND@4") (pinfunction "GND_GND@4") (pintype "bidirectional"))
    )
    (net (code "64") (name "unconnected-(B1-Pad3.3V)") (class "Default")
      (node (ref "B1") (pin "3.3V") (pinfunction "3.3V_3.3V") (pintype "bidirectional"))
    )
    (net (code "65") (name "unconnected-(B1-Pad47)") (class "Default")
      (node (ref "B1") (pin "47") (pinfunction "47_47") (pintype "bidirectional"))
    )
    (net (code "66") (name "unconnected-(B1-PadAREF)") (class "Default")
      (node (ref "B1") (pin "AREF") (pinfunction "AREF_AREF") (pintype "bidirectional"))
    )
    (net (code "67") (name "unconnected-(B1-PadRESET)") (class "Default")
      (node (ref "B1") (pin "RESET") (pinfunction "RESET_RESET") (pintype "bidirectional"))
    )
    (net (code "68") (name "unconnected-(D-Pad1)") (class "Default")
      (node (ref "D") (pin "1") (pinfunction "1_1") (pintype "bidirectional"))
    )
    (net (code "69") (name "unconnected-(D-Pad2)") (class "Default")
      (node (ref "D") (pin "2") (pinfunction "2_2") (pintype "bidirectional"))
    )
    (net (code "70") (name "unconnected-(D-Pad3)") (class "Default")
      (node (ref "D") (pin "3") (pinfunction "3_3") (pintype "bidirectional"))
    )
    (net (code "71") (name "unconnected-(D-Pad4)") (class "Default")
      (node (ref "D") (pin "4") (pinfunction "4_4") (pintype "bidirectional"))
    )
    (net (code "72") (name "unconnected-(PWROUTA-KL-Pad1)") (class "Default")
      (node (ref "PWROUT") (pin "1") (pinfunction "KL_1") (pintype "passive"))
    )
    (net (code "73") (name "unconnected-(PWROUTB-KL-Pad2)") (class "Default")
      (node (ref "PWROUT") (pin "2") (pinfunction "KL_2") (pintype "passive"))
    )
    (net (code "74") (name "unconnected-(PWROUTC-KL-Pad3)") (class "Default")
      (node (ref "PWROUT") (pin "3") (pinfunction "KL_3") (pintype "passive"))
    )
    (net (code "75") (name "unconnected-(PWROUTD-KL-Pad4)") (class "Default")
      (node (ref "PWROUT") (pin "4") (pinfunction "KL_4") (pintype "passive"))
    )
    (net (code "76") (name "unconnected-(XINA-KL-Pad1)") (class "Default")
      (node (ref "XIN") (pin "1") (pinfunction "KL_1") (pintype "passive"))
    )
  )
)
